# boarduino_2.net
KiCad netlist of a schematic drawn in EAGLE
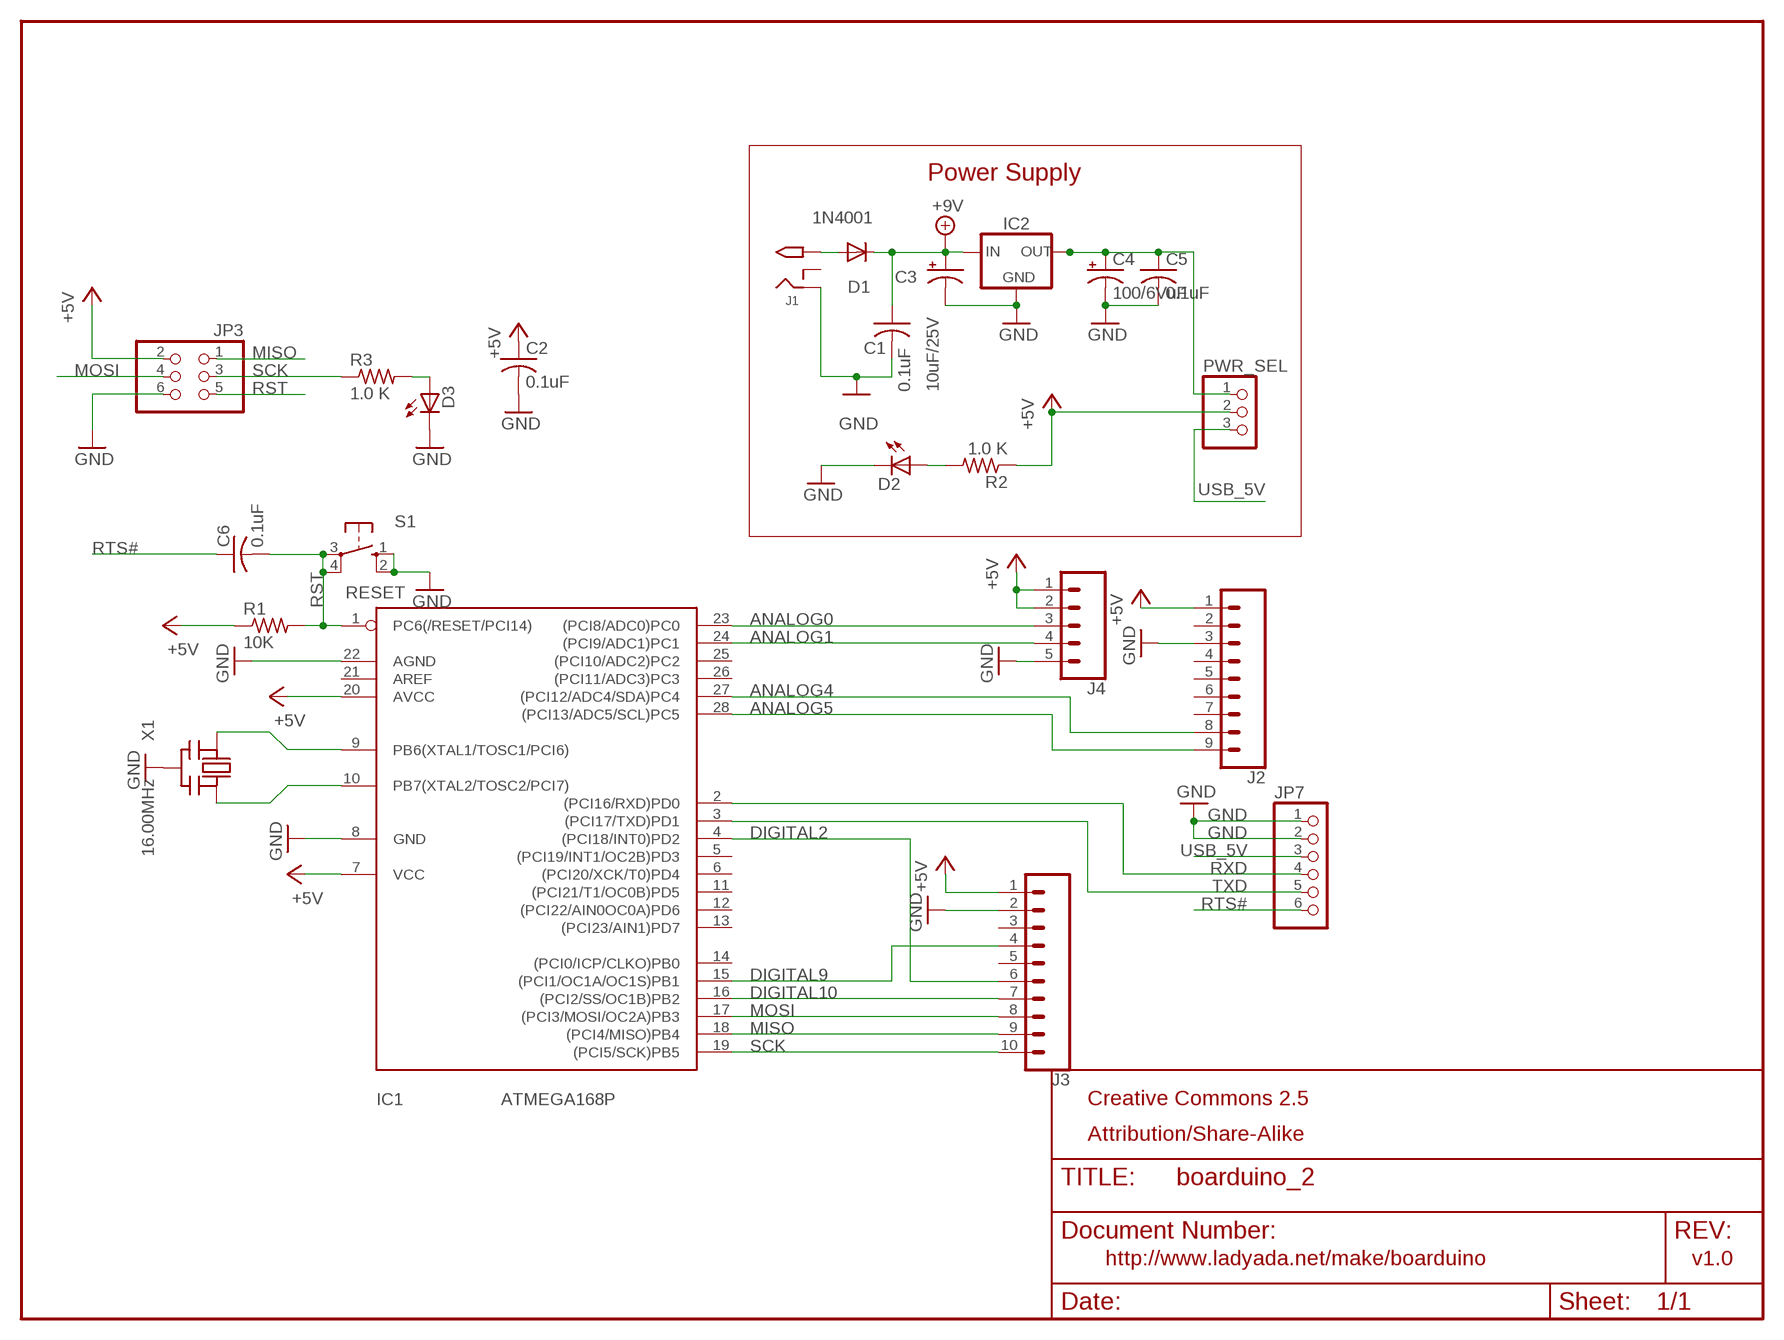
[diagram p0: schematic, sheet 1]

(export (version "E")
  (design (tool "Eeschema 10.0.6"))
  (components
    (comp (ref "C1")
      (value "0.1uF")
      (footprint "eagle-import:C025-025X050")
      (libsource (lib "eagle-import") (part "C-US025-025X050"))
    )
    (comp (ref "C2")
      (value "0.1uF")
      (footprint "eagle-import:C025-025X050")
      (libsource (lib "eagle-import") (part "C-US025-025X050"))
    )
    (comp (ref "C3")
      (value "10uF/25V")
      (footprint "eagle-import:E2,5-6")
      (libsource (lib "eagle-import") (part "CPOL-USE2.5-6"))
    )
    (comp (ref "C4")
      (value "100/6VuF")
      (footprint "eagle-import:E2,5-6")
      (libsource (lib "eagle-import") (part "CPOL-USE2.5-6"))
    )
    (comp (ref "C5")
      (value "0.1uF")
      (footprint "eagle-import:C025-025X050")
      (libsource (lib "eagle-import") (part "C-US025-025X050"))
    )
    (comp (ref "C6")
      (value "0.1uF")
      (footprint "eagle-import:C025-025X050")
      (libsource (lib "eagle-import") (part "C-US025-025X050"))
    )
    (comp (ref "D1")
      (value "1N4001")
      (footprint "eagle-import:DO41-10")
      (libsource (lib "eagle-import") (part "1N4004"))
    )
    (comp (ref "D2")
      (value "LED3MM")
      (footprint "eagle-import:LED3MM")
      (libsource (lib "eagle-import") (part "LED3MM"))
    )
    (comp (ref "D3")
      (value "Green")
      (footprint "eagle-import:LED3MM")
      (libsource (lib "eagle-import") (part "LED3MM"))
    )
    (comp (ref "IC1")
      (value "ATMEGA168P")
      (footprint "eagle-import:DIL28_3")
      (libsource (lib "eagle-import") (part "ATMEGA168PROUND"))
    )
    (comp (ref "IC2")
      (value "78XXS")
      (footprint "eagle-import:78XXS")
      (libsource (lib "eagle-import") (part "78XXS"))
    )
    (comp (ref "J1")
      (value "2.1MMJACK")
      (footprint "eagle-import:PJ-102A")
      (libsource (lib "eagle-import") (part "2.1MMJACK"))
    )
    (comp (ref "J2")
      (value "CONN_09")
      (footprint "eagle-import:1X09")
      (libsource (lib "eagle-import") (part "CONN_09"))
    )
    (comp (ref "J3")
      (value "CONN_10\"")
      (footprint "eagle-import:1X10")
      (libsource (lib "eagle-import") (part "CONN_10{dblquote}"))
    )
    (comp (ref "J4")
      (value "CONN_05")
      (footprint "eagle-import:1X05")
      (libsource (lib "eagle-import") (part "CONN_05"))
    )
    (comp (ref "JP3")
      (value "PINHD-2X3")
      (footprint "eagle-import:2X03")
      (libsource (lib "eagle-import") (part "PINHD-2X3"))
    )
    (comp (ref "JP7")
      (value "PINHD-1X6CLEAN")
      (footprint "eagle-import:1X06-CLEAN")
      (libsource (lib "eagle-import") (part "PINHD-1X6CLEAN"))
    )
    (comp (ref "PWR_SEL")
      (value "PINHD-1X3")
      (footprint "eagle-import:1X03")
      (libsource (lib "eagle-import") (part "PINHD-1X3"))
    )
    (comp (ref "R1")
      (value "10K")
      (footprint "eagle-import:0207_5V")
      (libsource (lib "eagle-import") (part "rcl-ez_R-US_0207/5V"))
    )
    (comp (ref "R2")
      (value "1.0 K")
      (footprint "eagle-import:0207_5V")
      (libsource (lib "eagle-import") (part "R-US_0207/5V"))
    )
    (comp (ref "R3")
      (value "1.0 K")
      (footprint "eagle-import:0207_5V")
      (libsource (lib "eagle-import") (part "R-US_0207/5V"))
    )
    (comp (ref "S1")
      (value "RESET")
      (footprint "eagle-import:B3F-10XX")
      (libsource (lib "eagle-import") (part "10-XX"))
    )
    (comp (ref "X1")
      (value "16.00MHz")
      (footprint "eagle-import:CERM_OSC")
      (libsource (lib "eagle-import") (part "CERMOSCILL"))
    )
  )
  (nets
    (net (code "1") (name "+5V") (class "Default")
      (node (ref "C2") (pin "1") (pinfunction "1_1") (pintype "passive"))
      (node (ref "IC1") (pin "20") (pinfunction "AVCC_20") (pintype "bidirectional"))
      (node (ref "IC1") (pin "7") (pinfunction "VCC_7") (pintype "bidirectional"))
      (node (ref "J2") (pin "1") (pinfunction "1_1") (pintype "passive"))
      (node (ref "J3") (pin "1") (pinfunction "1_1") (pintype "passive"))
      (node (ref "J4") (pin "1") (pinfunction "1_1") (pintype "passive"))
      (node (ref "J4") (pin "2") (pinfunction "2_2") (pintype "passive"))
      (node (ref "JP3") (pin "2") (pinfunction "2_2") (pintype "passive"))
      (node (ref "PWR_SEL") (pin "2") (pinfunction "2_2") (pintype "passive"))
      (node (ref "R1") (pin "1") (pinfunction "1_1") (pintype "passive"))
      (node (ref "R2") (pin "1") (pinfunction "1_1") (pintype "passive"))
    )
    (net (code "2") (name "+9V") (class "Default")
      (node (ref "C1") (pin "1") (pinfunction "1_1") (pintype "passive"))
      (node (ref "C3") (pin "+") (pinfunction "+_+") (pintype "passive"))
      (node (ref "D1") (pin "C") (pinfunction "C_C") (pintype "passive"))
      (node (ref "IC2") (pin "IN") (pinfunction "IN_IN") (pintype "input"))
    )
    (net (code "3") (name "/ANALOG0") (class "Default")
      (node (ref "IC1") (pin "23") (pinfunction "(PCI8/ADC0)PC0_23") (pintype "bidirectional"))
      (node (ref "J4") (pin "3") (pinfunction "3_3") (pintype "passive"))
    )
    (net (code "4") (name "/ANALOG1") (class "Default")
      (node (ref "IC1") (pin "24") (pinfunction "(PCI9/ADC1)PC1_24") (pintype "bidirectional"))
      (node (ref "J4") (pin "4") (pinfunction "4_4") (pintype "passive"))
    )
    (net (code "5") (name "/ANALOG4") (class "Default")
      (node (ref "IC1") (pin "27") (pinfunction "(PCI12/ADC4/SDA)PC4_27") (pintype "bidirectional"))
      (node (ref "J2") (pin "8") (pinfunction "8_8") (pintype "passive"))
    )
    (net (code "6") (name "/ANALOG5") (class "Default")
      (node (ref "IC1") (pin "28") (pinfunction "(PCI13/ADC5/SCL)PC5_28") (pintype "bidirectional"))
      (node (ref "J2") (pin "9") (pinfunction "9_9") (pintype "passive"))
    )
    (net (code "7") (name "/DIGITAL2") (class "Default")
      (node (ref "IC1") (pin "4") (pinfunction "(PCI18/INT0)PD2_4") (pintype "bidirectional"))
      (node (ref "J3") (pin "6") (pinfunction "6_6") (pintype "passive"))
    )
    (net (code "8") (name "/DIGITAL9") (class "Default")
      (node (ref "IC1") (pin "15") (pinfunction "(PCI1/OC1A/OC1S)PB1_15") (pintype "bidirectional"))
      (node (ref "J3") (pin "4") (pinfunction "4_4") (pintype "passive"))
    )
    (net (code "9") (name "/DIGITAL10") (class "Default")
      (node (ref "IC1") (pin "16") (pinfunction "(PCI2/SS/OC1B)PB2_16") (pintype "bidirectional"))
      (node (ref "J3") (pin "7") (pinfunction "7_7") (pintype "passive"))
    )
    (net (code "10") (name "/MISO") (class "Default")
      (node (ref "IC1") (pin "18") (pinfunction "(PCI4/MISO)PB4_18") (pintype "bidirectional"))
      (node (ref "J3") (pin "9") (pinfunction "9_9") (pintype "passive"))
      (node (ref "JP3") (pin "1") (pinfunction "1_1") (pintype "passive"))
    )
    (net (code "11") (name "/MOSI") (class "Default")
      (node (ref "IC1") (pin "17") (pinfunction "(PCI3/MOSI/OC2A)PB3_17") (pintype "bidirectional"))
      (node (ref "J3") (pin "8") (pinfunction "8_8") (pintype "passive"))
      (node (ref "JP3") (pin "4") (pinfunction "4_4") (pintype "passive"))
    )
    (net (code "12") (name "/RST") (class "Default")
      (node (ref "C6") (pin "2") (pinfunction "2_2") (pintype "passive"))
      (node (ref "IC1") (pin "1") (pinfunction "PC6(/RESET/PCI14)_1") (pintype "bidirectional"))
      (node (ref "JP3") (pin "5") (pinfunction "5_5") (pintype "passive"))
      (node (ref "R1") (pin "2") (pinfunction "2_2") (pintype "passive"))
      (node (ref "S1") (pin "3") (pinfunction "P_3") (pintype "passive"))
      (node (ref "S1") (pin "4") (pinfunction "P1_4") (pintype "passive"))
    )
    (net (code "13") (name "/RTS#") (class "Default")
      (node (ref "C6") (pin "1") (pinfunction "1_1") (pintype "passive"))
      (node (ref "JP7") (pin "6") (pinfunction "6_6") (pintype "passive"))
    )
    (net (code "14") (name "/RXD") (class "Default")
      (node (ref "IC1") (pin "2") (pinfunction "(PCI16/RXD)PD0_2") (pintype "bidirectional"))
      (node (ref "JP7") (pin "4") (pinfunction "4_4") (pintype "passive"))
    )
    (net (code "15") (name "/SCK") (class "Default")
      (node (ref "IC1") (pin "19") (pinfunction "(PCI5/SCK)PB5_19") (pintype "bidirectional"))
      (node (ref "J3") (pin "10") (pinfunction "10_10") (pintype "passive"))
      (node (ref "JP3") (pin "3") (pinfunction "3_3") (pintype "passive"))
      (node (ref "R3") (pin "1") (pinfunction "1_1") (pintype "passive"))
    )
    (net (code "16") (name "/TXD") (class "Default")
      (node (ref "IC1") (pin "3") (pinfunction "(PCI17/TXD)PD1_3") (pintype "bidirectional"))
      (node (ref "JP7") (pin "5") (pinfunction "5_5") (pintype "passive"))
    )
    (net (code "17") (name "/USB_5V") (class "Default")
      (node (ref "JP7") (pin "3") (pinfunction "3_3") (pintype "passive"))
      (node (ref "PWR_SEL") (pin "3") (pinfunction "3_3") (pintype "passive"))
    )
    (net (code "18") (name "GND") (class "Default")
      (node (ref "C1") (pin "2") (pinfunction "2_2") (pintype "passive"))
      (node (ref "C2") (pin "2") (pinfunction "2_2") (pintype "passive"))
      (node (ref "C3") (pin "-") (pinfunction "-_-") (pintype "passive"))
      (node (ref "C4") (pin "-") (pinfunction "-_-") (pintype "passive"))
      (node (ref "C5") (pin "2") (pinfunction "2_2") (pintype "passive"))
      (node (ref "D2") (pin "K") (pinfunction "C_K") (pintype "passive"))
      (node (ref "D3") (pin "K") (pinfunction "C_K") (pintype "passive"))
      (node (ref "IC1") (pin "22") (pinfunction "AGND_22") (pintype "bidirectional"))
      (node (ref "IC1") (pin "8") (pinfunction "GND_8") (pintype "bidirectional"))
      (node (ref "IC2") (pin "GND") (pinfunction "GND_GND") (pintype "input"))
      (node (ref "J1") (pin "RING") (pinfunction "RING_RING") (pintype "bidirectional"))
      (node (ref "J2") (pin "3") (pinfunction "3_3") (pintype "passive"))
      (node (ref "J3") (pin "2") (pinfunction "2_2") (pintype "passive"))
      (node (ref "J4") (pin "5") (pinfunction "5_5") (pintype "passive"))
      (node (ref "JP3") (pin "6") (pinfunction "6_6") (pintype "passive"))
      (node (ref "JP7") (pin "1") (pinfunction "1_1") (pintype "passive"))
      (node (ref "JP7") (pin "2") (pinfunction "2_2") (pintype "passive"))
      (node (ref "S1") (pin "1") (pinfunction "S_1") (pintype "passive"))
      (node (ref "S1") (pin "2") (pinfunction "S1_2") (pintype "passive"))
      (node (ref "X1") (pin "P$2") (pinfunction "GND_P$2") (pintype "bidirectional"))
    )
    (net (code "19") (name "Net-(C4-Pad+)") (class "Default")
      (node (ref "C4") (pin "+") (pinfunction "+_+") (pintype "passive"))
      (node (ref "C5") (pin "1") (pinfunction "1_1") (pintype "passive"))
      (node (ref "IC2") (pin "OUT") (pinfunction "OUT_OUT") (pintype "passive"))
      (node (ref "PWR_SEL") (pin "1") (pinfunction "1_1") (pintype "passive"))
    )
    (net (code "20") (name "Net-(D1-PadA)") (class "Default")
      (node (ref "D1") (pin "A") (pinfunction "A_A") (pintype "passive"))
      (node (ref "J1") (pin "TIP") (pinfunction "TIP_TIP") (pintype "bidirectional"))
    )
    (net (code "21") (name "Net-(D2-PadA)") (class "Default")
      (node (ref "D2") (pin "A") (pinfunction "A_A") (pintype "passive"))
      (node (ref "R2") (pin "2") (pinfunction "2_2") (pintype "passive"))
    )
    (net (code "22") (name "Net-(D3-PadA)") (class "Default")
      (node (ref "D3") (pin "A") (pinfunction "A_A") (pintype "passive"))
      (node (ref "R3") (pin "2") (pinfunction "2_2") (pintype "passive"))
    )
    (net (code "23") (name "Net-(IC1-PB6(XTAL1{slash}TOSC1{slash}PCI6))") (class "Default")
      (node (ref "IC1") (pin "9") (pinfunction "PB6(XTAL1/TOSC1/PCI6)_9") (pintype "bidirectional"))
      (node (ref "X1") (pin "P$1") (pinfunction "IN_P$1") (pintype "bidirectional"))
    )
    (net (code "24") (name "Net-(IC1-PB7(XTAL2{slash}TOSC2{slash}PCI7))") (class "Default")
      (node (ref "IC1") (pin "10") (pinfunction "PB7(XTAL2/TOSC2/PCI7)_10") (pintype "bidirectional"))
      (node (ref "X1") (pin "P$3") (pinfunction "OUT_P$3") (pintype "bidirectional"))
    )
    (net (code "25") (name "unconnected-(IC1-(PCI0{slash}ICP{slash}CLKO)PB0-Pad14)") (class "Default")
      (node (ref "IC1") (pin "14") (pinfunction "(PCI0/ICP/CLKO)PB0_14") (pintype "bidirectional"))
    )
    (net (code "26") (name "unconnected-(IC1-(PCI10{slash}ADC2)PC2-Pad25)") (class "Default")
      (node (ref "IC1") (pin "25") (pinfunction "(PCI10/ADC2)PC2_25") (pintype "bidirectional"))
    )
    (net (code "27") (name "unconnected-(IC1-(PCI11{slash}ADC3)PC3-Pad26)") (class "Default")
      (node (ref "IC1") (pin "26") (pinfunction "(PCI11/ADC3)PC3_26") (pintype "bidirectional"))
    )
    (net (code "28") (name "unconnected-(IC1-(PCI19{slash}INT1{slash}OC2B)PD3-Pad5)") (class "Default")
      (node (ref "IC1") (pin "5") (pinfunction "(PCI19/INT1/OC2B)PD3_5") (pintype "bidirectional"))
    )
    (net (code "29") (name "unconnected-(IC1-(PCI20{slash}XCK{slash}T0)PD4-Pad6)") (class "Default")
      (node (ref "IC1") (pin "6") (pinfunction "(PCI20/XCK/T0)PD4_6") (pintype "bidirectional"))
    )
    (net (code "30") (name "unconnected-(IC1-(PCI21{slash}T1{slash}OC0B)PD5-Pad11)") (class "Default")
      (node (ref "IC1") (pin "11") (pinfunction "(PCI21/T1/OC0B)PD5_11") (pintype "bidirectional"))
    )
    (net (code "31") (name "unconnected-(IC1-(PCI22{slash}AIN0OC0A)PD6-Pad12)") (class "Default")
      (node (ref "IC1") (pin "12") (pinfunction "(PCI22/AIN0OC0A)PD6_12") (pintype "bidirectional"))
    )
    (net (code "32") (name "unconnected-(IC1-(PCI23{slash}AIN1)PD7-Pad13)") (class "Default")
      (node (ref "IC1") (pin "13") (pinfunction "(PCI23/AIN1)PD7_13") (pintype "bidirectional"))
    )
    (net (code "33") (name "unconnected-(IC1-AREF-Pad21)") (class "Default")
      (node (ref "IC1") (pin "21") (pinfunction "AREF_21") (pintype "bidirectional"))
    )
    (net (code "34") (name "unconnected-(J1-PadRING_SW)") (class "Default")
      (node (ref "J1") (pin "RING_SW") (pinfunction "RING_SW_RING_SW") (pintype "bidirectional"))
    )
    (net (code "35") (name "unconnected-(J2-Pad2)") (class "Default")
      (node (ref "J2") (pin "2") (pinfunction "2_2") (pintype "passive"))
    )
    (net (code "36") (name "unconnected-(J2-Pad4)") (class "Default")
      (node (ref "J2") (pin "4") (pinfunction "4_4") (pintype "passive"))
    )
    (net (code "37") (name "unconnected-(J2-Pad5)") (class "Default")
      (node (ref "J2") (pin "5") (pinfunction "5_5") (pintype "passive"))
    )
    (net (code "38") (name "unconnected-(J2-Pad6)") (class "Default")
      (node (ref "J2") (pin "6") (pinfunction "6_6") (pintype "passive"))
    )
    (net (code "39") (name "unconnected-(J2-Pad7)") (class "Default")
      (node (ref "J2") (pin "7") (pinfunction "7_7") (pintype "passive"))
    )
    (net (code "40") (name "unconnected-(J3-Pad3)") (class "Default")
      (node (ref "J3") (pin "3") (pinfunction "3_3") (pintype "passive"))
    )
    (net (code "41") (name "unconnected-(J3-Pad5)") (class "Default")
      (node (ref "J3") (pin "5") (pinfunction "5_5") (pintype "passive"))
    )
  )
)
